# bicyclelab-manager-v3.net
KiCad netlist of a schematic drawn in EAGLE
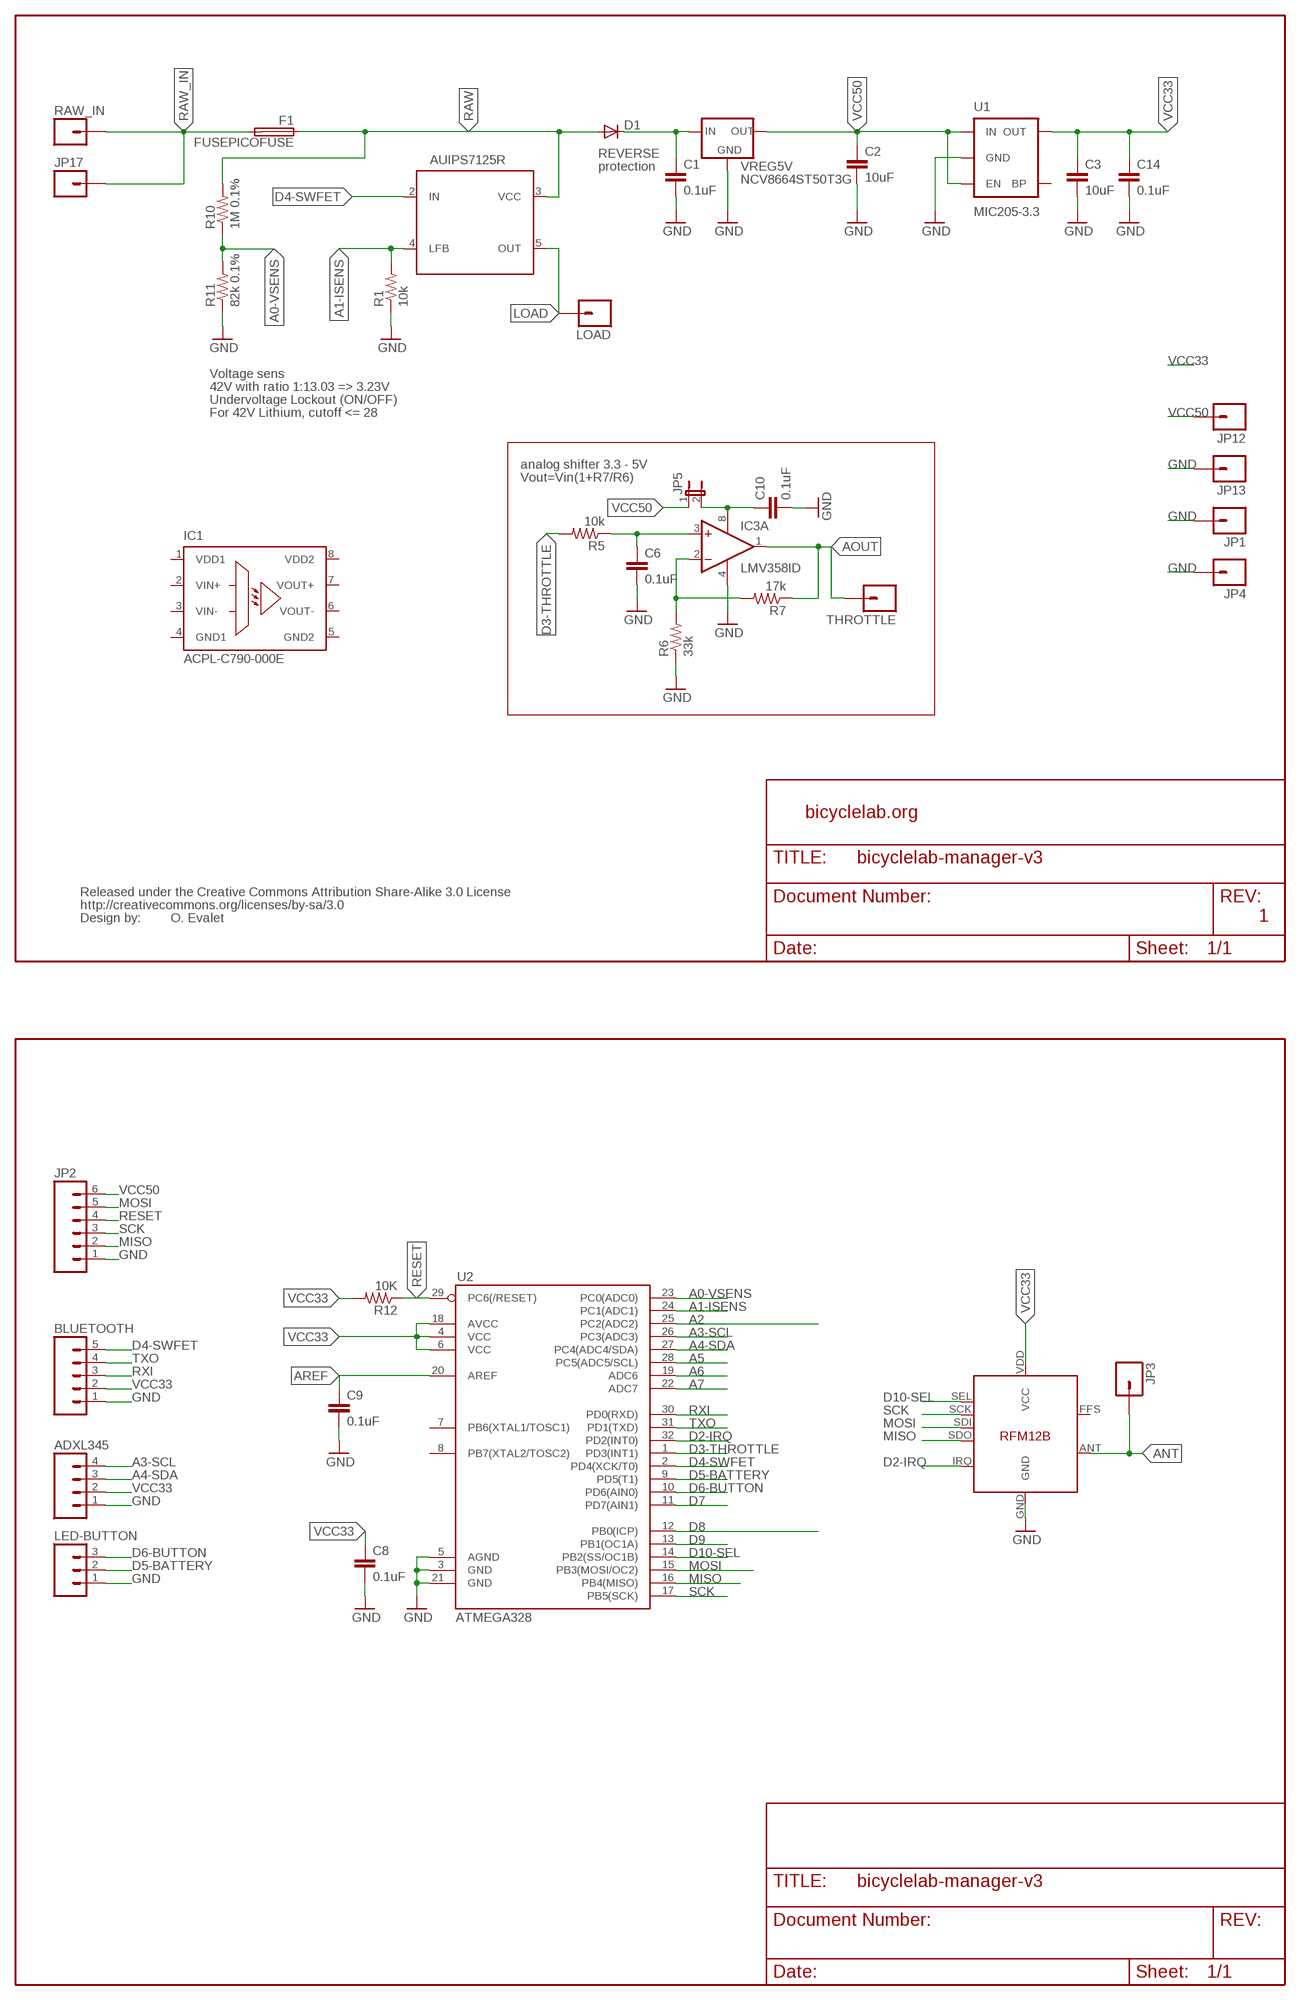
[diagram p0: schematic, sheet 1]

(export (version "E")
  (design (tool "Eeschema 10.0.6"))
  (components
    (comp (ref "ADXL345")
      (value "M04PTH")
      (footprint "eagle-import:1X04")
      (libsource (lib "eagle-import") (part "M04PTH"))
    )
    (comp (ref "BLUETOOTH")
      (value "M05PTH")
      (footprint "eagle-import:1X05")
      (libsource (lib "eagle-import") (part "M05PTH"))
    )
    (comp (ref "C1")
      (value "0.1uF")
      (footprint "eagle-import:0805")
      (libsource (lib "eagle-import") (part "CAP0805"))
    )
    (comp (ref "C2")
      (value "10uF")
      (footprint "eagle-import:0805")
      (libsource (lib "eagle-import") (part "CAP0805"))
    )
    (comp (ref "C3")
      (value "10uF")
      (footprint "eagle-import:0805")
      (libsource (lib "eagle-import") (part "CAP0805"))
    )
    (comp (ref "C6")
      (value "0.1uF")
      (footprint "eagle-import:0805")
      (libsource (lib "eagle-import") (part "CAP0805"))
    )
    (comp (ref "C8")
      (value "0.1uF")
      (footprint "eagle-import:0603-CAP")
      (libsource (lib "eagle-import") (part "CAP0603-CAP"))
    )
    (comp (ref "C9")
      (value "0.1uF")
      (footprint "eagle-import:0603-CAP")
      (libsource (lib "eagle-import") (part "CAP0603-CAP"))
    )
    (comp (ref "C10")
      (value "0.1uF")
      (footprint "eagle-import:0805")
      (libsource (lib "eagle-import") (part "CAP0805"))
    )
    (comp (ref "C14")
      (value "0.1uF")
      (footprint "eagle-import:0603-CAP")
      (libsource (lib "eagle-import") (part "CAP0603-CAP"))
    )
    (comp (ref "D1")
      (value "DIODESOD")
      (footprint "eagle-import:SOD-323")
      (libsource (lib "eagle-import") (part "DIODESOD"))
    )
    (comp (ref "F1")
      (value "FUSEPICOFUSE")
      (footprint "eagle-import:PICOFUSE")
      (libsource (lib "eagle-import") (part "FUSEPICOFUSE"))
    )
    (comp (ref "IC1")
      (value "ACPL-C790-000E")
      (footprint "eagle-import:DIP8")
      (libsource (lib "eagle-import") (part "ACPL-790A"))
    )
    (comp (ref "IC3")
      (value "LMV358ID")
      (footprint "eagle-import:SO08")
      (libsource (lib "eagle-import") (part "MCP602SN"))
    )
    (comp (ref "JP1")
      (value "M01PTH_2MM")
      (footprint "eagle-import:1X01_2MM")
      (libsource (lib "eagle-import") (part "SparkFun_M01PTH_2MM"))
    )
    (comp (ref "JP2")
      (value "M06EM406")
      (footprint "eagle-import:EM406")
      (libsource (lib "eagle-import") (part "M06EM406"))
    )
    (comp (ref "JP3")
      (value "M01SMD-4.5X1.5")
      (footprint "eagle-import:PAD-1.5X4.5")
      (libsource (lib "eagle-import") (part "M01SMD-4.5X1.5"))
    )
    (comp (ref "JP4")
      (value "M01PTH_2MM")
      (footprint "eagle-import:1X01_2MM")
      (libsource (lib "eagle-import") (part "SparkFun_M01PTH_2MM"))
    )
    (comp (ref "JP5")
      (value "JUMPER-2PTH_LOCK")
      (footprint "eagle-import:1X02_LOCK")
      (libsource (lib "eagle-import") (part "JUMPER-2PTH_LOCK"))
    )
    (comp (ref "JP12")
      (value "M01PTH")
      (footprint "eagle-import:1X01")
      (libsource (lib "eagle-import") (part "SparkFun_M01PTH"))
    )
    (comp (ref "JP13")
      (value "M01PTH")
      (footprint "eagle-import:1X01")
      (libsource (lib "eagle-import") (part "SparkFun_M01PTH"))
    )
    (comp (ref "JP17")
      (value "M01PTH_2MM")
      (footprint "eagle-import:1X01_2MM")
      (libsource (lib "eagle-import") (part "SparkFun_M01PTH_2MM"))
    )
    (comp (ref "LED-BUTTON")
      (value "M03PTH")
      (footprint "eagle-import:1X03")
      (libsource (lib "eagle-import") (part "M03PTH"))
    )
    (comp (ref "LOAD")
      (value "M01PTH_2MM")
      (footprint "eagle-import:1X01_2MM")
      (libsource (lib "eagle-import") (part "SparkFun_M01PTH_2MM"))
    )
    (comp (ref "R1")
      (value "10k")
      (footprint "eagle-import:0805")
      (libsource (lib "eagle-import") (part "RESISTOR"))
    )
    (comp (ref "R5")
      (value "10k")
      (footprint "eagle-import:0805")
      (libsource (lib "eagle-import") (part "RESISTOR"))
    )
    (comp (ref "R6")
      (value "33k")
      (footprint "eagle-import:0805")
      (libsource (lib "eagle-import") (part "RESISTOR"))
    )
    (comp (ref "R7")
      (value "17k")
      (footprint "eagle-import:0805")
      (libsource (lib "eagle-import") (part "RESISTOR"))
    )
    (comp (ref "R10")
      (value "1M 0.1%")
      (footprint "eagle-import:0805")
      (libsource (lib "eagle-import") (part "RESISTOR"))
    )
    (comp (ref "R11")
      (value "82k 0.1%")
      (footprint "eagle-import:0805")
      (libsource (lib "eagle-import") (part "RESISTOR"))
    )
    (comp (ref "R12")
      (value "10K")
      (footprint "eagle-import:0603-RES")
      (libsource (lib "eagle-import") (part "RESISTOR0603-RES"))
    )
    (comp (ref "RAW_IN")
      (value "M01PTH_2MM")
      (footprint "eagle-import:1X01_2MM")
      (libsource (lib "eagle-import") (part "SparkFun_M01PTH_2MM"))
    )
    (comp (ref "THROTTLE")
      (value "M01PTH")
      (footprint "eagle-import:1X01")
      (libsource (lib "eagle-import") (part "SparkFun_M01PTH"))
    )
    (comp (ref "U$1")
      (value "RFM12B")
      (footprint "eagle-import:RFM12B")
      (libsource (lib "eagle-import") (part "RFM12B"))
    )
    (comp (ref "U$5")
      (value "CREATIVE_COMMONS")
      (footprint "eagle-import:CREATIVE_COMMONS")
      (libsource (lib "eagle-import") (part "CREATIVE_COMMONS"))
    )
    (comp (ref "U$8")
      (value "AUIPS7125R")
      (footprint "eagle-import:DPAK-5")
      (libsource (lib "eagle-import") (part "AUIPS7125R"))
    )
    (comp (ref "U1")
      (value "MIC205-3.3")
      (footprint "eagle-import:SOT23-5")
      (libsource (lib "eagle-import") (part "V_REG_LDOSMD"))
    )
    (comp (ref "U2")
      (value "ATMEGA328")
      (footprint "eagle-import:TQFP32-08")
      (libsource (lib "eagle-import") (part "ATMEGA168"))
    )
    (comp (ref "VREG5V")
      (value "NCV8664ST50T3G")
      (footprint "eagle-import:SOT223")
      (libsource (lib "eagle-import") (part "V_REG_MIC2920"))
    )
  )
  (nets
    (net (code "1") (name "/A2") (class "Default")
      (node (ref "U2") (pin "25") (pinfunction "PC2(ADC2)_25") (pintype "bidirectional"))
    )
    (net (code "2") (name "/A3-SCL") (class "Default")
      (node (ref "ADXL345") (pin "4") (pinfunction "4_4") (pintype "passive"))
      (node (ref "U2") (pin "26") (pinfunction "PC3(ADC3)_26") (pintype "bidirectional"))
    )
    (net (code "3") (name "/A4-SDA") (class "Default")
      (node (ref "ADXL345") (pin "3") (pinfunction "3_3") (pintype "passive"))
      (node (ref "U2") (pin "27") (pinfunction "PC4(ADC4/SDA)_27") (pintype "bidirectional"))
    )
    (net (code "4") (name "/A5") (class "Default")
      (node (ref "U2") (pin "28") (pinfunction "PC5(ADC5/SCL)_28") (pintype "bidirectional"))
    )
    (net (code "5") (name "/A6") (class "Default")
      (node (ref "U2") (pin "19") (pinfunction "ADC6_19") (pintype "bidirectional"))
    )
    (net (code "6") (name "/A7") (class "Default")
      (node (ref "U2") (pin "22") (pinfunction "ADC7_22") (pintype "bidirectional"))
    )
    (net (code "7") (name "/D2-IRQ") (class "Default")
      (node (ref "U$1") (pin "IRQ") (pinfunction "IRQ_IRQ") (pintype "open_collector"))
      (node (ref "U2") (pin "32") (pinfunction "PD2(INT0)_32") (pintype "bidirectional"))
    )
    (net (code "8") (name "/D5-BATTERY") (class "Default")
      (node (ref "LED-BUTTON") (pin "2") (pinfunction "2_2") (pintype "passive"))
      (node (ref "U2") (pin "9") (pinfunction "PD5(T1)_9") (pintype "bidirectional"))
    )
    (net (code "9") (name "/D6-BUTTON") (class "Default")
      (node (ref "LED-BUTTON") (pin "3") (pinfunction "3_3") (pintype "passive"))
      (node (ref "U2") (pin "10") (pinfunction "PD6(AIN0)_10") (pintype "bidirectional"))
    )
    (net (code "10") (name "/D7") (class "Default")
      (node (ref "U2") (pin "11") (pinfunction "PD7(AIN1)_11") (pintype "bidirectional"))
    )
    (net (code "11") (name "/D8") (class "Default")
      (node (ref "U2") (pin "12") (pinfunction "PB0(ICP)_12") (pintype "bidirectional"))
    )
    (net (code "12") (name "/D9") (class "Default")
      (node (ref "U2") (pin "13") (pinfunction "PB1(OC1A)_13") (pintype "bidirectional"))
    )
    (net (code "13") (name "/D10-SEL") (class "Default")
      (node (ref "U$1") (pin "SEL") (pinfunction "SEL_SEL") (pintype "input"))
      (node (ref "U2") (pin "14") (pinfunction "PB2(SS/OC1B)_14") (pintype "bidirectional"))
    )
    (net (code "14") (name "/GND1") (class "Default")
      (node (ref "IC1") (pin "4") (pinfunction "GND1_4") (pintype "power_in"))
    )
    (net (code "15") (name "/GND2") (class "Default")
      (node (ref "IC1") (pin "5") (pinfunction "GND2_5") (pintype "power_in"))
    )
    (net (code "16") (name "/MISO") (class "Default")
      (node (ref "JP2") (pin "2") (pinfunction "2_2") (pintype "passive"))
      (node (ref "U$1") (pin "SDO") (pinfunction "SDO_SDO") (pintype "output"))
      (node (ref "U2") (pin "16") (pinfunction "PB4(MISO)_16") (pintype "bidirectional"))
    )
    (net (code "17") (name "/MOSI") (class "Default")
      (node (ref "JP2") (pin "5") (pinfunction "5_5") (pintype "passive"))
      (node (ref "U$1") (pin "SDI") (pinfunction "SDI_SDI") (pintype "input"))
      (node (ref "U2") (pin "15") (pinfunction "PB3(MOSI/OC2)_15") (pintype "bidirectional"))
    )
    (net (code "18") (name "/RXI") (class "Default")
      (node (ref "BLUETOOTH") (pin "3") (pinfunction "3_3") (pintype "passive"))
      (node (ref "U2") (pin "30") (pinfunction "PD0(RXD)_30") (pintype "bidirectional"))
    )
    (net (code "19") (name "/SCK") (class "Default")
      (node (ref "JP2") (pin "3") (pinfunction "3_3") (pintype "passive"))
      (node (ref "U$1") (pin "SCK") (pinfunction "SCK_SCK") (pintype "input"))
      (node (ref "U2") (pin "17") (pinfunction "PB5(SCK)_17") (pintype "bidirectional"))
    )
    (net (code "20") (name "/TXO") (class "Default")
      (node (ref "BLUETOOTH") (pin "4") (pinfunction "4_4") (pintype "passive"))
      (node (ref "U2") (pin "31") (pinfunction "PD1(TXD)_31") (pintype "bidirectional"))
    )
    (net (code "21") (name "/VDD1") (class "Default")
      (node (ref "IC1") (pin "1") (pinfunction "VDD1_1") (pintype "power_in"))
    )
    (net (code "22") (name "/VDD2") (class "Default")
      (node (ref "IC1") (pin "8") (pinfunction "VDD2_8") (pintype "power_in"))
    )
    (net (code "23") (name "/VIN+") (class "Default")
      (node (ref "IC1") (pin "2") (pinfunction "VIN+_2") (pintype "power_in"))
    )
    (net (code "24") (name "/VIN-") (class "Default")
      (node (ref "IC1") (pin "3") (pinfunction "VIN-_3") (pintype "power_in"))
    )
    (net (code "25") (name "/VOUT+") (class "Default")
      (node (ref "IC1") (pin "7") (pinfunction "VOUT+_7") (pintype "power_in"))
    )
    (net (code "26") (name "/VOUT-") (class "Default")
      (node (ref "IC1") (pin "6") (pinfunction "VOUT-_6") (pintype "power_in"))
    )
    (net (code "27") (name "A0-VSENS") (class "Default")
      (node (ref "R10") (pin "1") (pinfunction "1_1") (pintype "passive"))
      (node (ref "R11") (pin "2") (pinfunction "2_2") (pintype "passive"))
      (node (ref "U2") (pin "23") (pinfunction "PC0(ADC0)_23") (pintype "bidirectional"))
    )
    (net (code "28") (name "A1-ISENS") (class "Default")
      (node (ref "R1") (pin "2") (pinfunction "2_2") (pintype "passive"))
      (node (ref "U$8") (pin "4") (pinfunction "LFB_4") (pintype "output"))
      (node (ref "U2") (pin "24") (pinfunction "PC1(ADC1)_24") (pintype "bidirectional"))
    )
    (net (code "29") (name "ANT") (class "Default")
      (node (ref "JP3") (pin "P$1") (pinfunction "1_P$1") (pintype "passive"))
      (node (ref "U$1") (pin "ANT") (pinfunction "ANT_ANT") (pintype "passive"))
    )
    (net (code "30") (name "AOUT") (class "Default")
      (node (ref "IC3") (pin "1") (pinfunction "OUT_1") (pintype "output"))
      (node (ref "R7") (pin "1") (pinfunction "1_1") (pintype "passive"))
      (node (ref "THROTTLE") (pin "1") (pinfunction "1_1") (pintype "passive"))
    )
    (net (code "31") (name "AREF") (class "Default")
      (node (ref "C9") (pin "1") (pinfunction "1_1") (pintype "passive"))
      (node (ref "U2") (pin "20") (pinfunction "AREF_20") (pintype "bidirectional"))
    )
    (net (code "32") (name "D3-THROTTLE") (class "Default")
      (node (ref "R5") (pin "2") (pinfunction "2_2") (pintype "passive"))
      (node (ref "U2") (pin "1") (pinfunction "PD3(INT1)_1") (pintype "bidirectional"))
    )
    (net (code "33") (name "D4-SWFET") (class "Default")
      (node (ref "BLUETOOTH") (pin "5") (pinfunction "5_5") (pintype "passive"))
      (node (ref "U$8") (pin "2") (pinfunction "IN_2") (pintype "input"))
      (node (ref "U2") (pin "2") (pinfunction "PD4(XCK/T0)_2") (pintype "bidirectional"))
    )
    (net (code "34") (name "GND") (class "Default")
      (node (ref "ADXL345") (pin "1") (pinfunction "1_1") (pintype "passive"))
      (node (ref "BLUETOOTH") (pin "1") (pinfunction "1_1") (pintype "passive"))
      (node (ref "C1") (pin "2") (pinfunction "2_2") (pintype "passive"))
      (node (ref "C10") (pin "2") (pinfunction "2_2") (pintype "passive"))
      (node (ref "C14") (pin "2") (pinfunction "2_2") (pintype "passive"))
      (node (ref "C2") (pin "2") (pinfunction "2_2") (pintype "passive"))
      (node (ref "C3") (pin "2") (pinfunction "2_2") (pintype "passive"))
      (node (ref "C6") (pin "2") (pinfunction "2_2") (pintype "passive"))
      (node (ref "C8") (pin "2") (pinfunction "2_2") (pintype "passive"))
      (node (ref "C9") (pin "2") (pinfunction "2_2") (pintype "passive"))
      (node (ref "IC3") (pin "4") (pinfunction "V-_4") (pintype "power_in"))
      (node (ref "JP1") (pin "1") (pinfunction "1_1") (pintype "passive"))
      (node (ref "JP13") (pin "1") (pinfunction "1_1") (pintype "passive"))
      (node (ref "JP2") (pin "1") (pinfunction "1_1") (pintype "passive"))
      (node (ref "JP4") (pin "1") (pinfunction "1_1") (pintype "passive"))
      (node (ref "LED-BUTTON") (pin "1") (pinfunction "1_1") (pintype "passive"))
      (node (ref "R1") (pin "1") (pinfunction "1_1") (pintype "passive"))
      (node (ref "R11") (pin "1") (pinfunction "1_1") (pintype "passive"))
      (node (ref "R6") (pin "1") (pinfunction "1_1") (pintype "passive"))
      (node (ref "U$1") (pin "GND") (pinfunction "GND_GND") (pintype "power_in"))
      (node (ref "U1") (pin "2") (pinfunction "GND_2") (pintype "input"))
      (node (ref "U2") (pin "21") (pinfunction "GND_21") (pintype "bidirectional"))
      (node (ref "U2") (pin "3") (pinfunction "GND_3") (pintype "bidirectional"))
      (node (ref "U2") (pin "5") (pinfunction "AGND_5") (pintype "bidirectional"))
      (node (ref "VREG5V") (pin "2") (pinfunction "GND_2") (pintype "input"))
    )
    (net (code "35") (name "LOAD") (class "Default")
      (node (ref "LOAD") (pin "1") (pinfunction "1_1") (pintype "passive"))
      (node (ref "U$8") (pin "5") (pinfunction "OUT_5") (pintype "output"))
    )
    (net (code "36") (name "Net-(D1-C)") (class "Default")
      (node (ref "C1") (pin "1") (pinfunction "1_1") (pintype "passive"))
      (node (ref "D1") (pin "1") (pinfunction "C_1") (pintype "passive"))
      (node (ref "VREG5V") (pin "1") (pinfunction "IN_1") (pintype "input"))
    )
    (net (code "37") (name "Net-(IC3A-+IN)") (class "Default")
      (node (ref "C6") (pin "1") (pinfunction "1_1") (pintype "passive"))
      (node (ref "IC3") (pin "3") (pinfunction "+IN_3") (pintype "input"))
      (node (ref "R5") (pin "1") (pinfunction "1_1") (pintype "passive"))
    )
    (net (code "38") (name "Net-(IC3A--IN)") (class "Default")
      (node (ref "IC3") (pin "2") (pinfunction "-IN_2") (pintype "input"))
      (node (ref "R6") (pin "2") (pinfunction "2_2") (pintype "passive"))
      (node (ref "R7") (pin "2") (pinfunction "2_2") (pintype "passive"))
    )
    (net (code "39") (name "Net-(IC3C-V+)") (class "Default")
      (node (ref "C10") (pin "1") (pinfunction "1_1") (pintype "passive"))
      (node (ref "IC3") (pin "8") (pinfunction "V+_8") (pintype "power_in"))
      (node (ref "JP5") (pin "2") (pinfunction "2_2") (pintype "passive"))
    )
    (net (code "40") (name "RAW") (class "Default")
      (node (ref "D1") (pin "2") (pinfunction "A_2") (pintype "passive"))
      (node (ref "F1") (pin "1") (pinfunction "1_1") (pintype "passive"))
      (node (ref "R10") (pin "2") (pinfunction "2_2") (pintype "passive"))
      (node (ref "U$8") (pin "3") (pinfunction "VCC_3") (pintype "input"))
    )
    (net (code "41") (name "RAW_IN") (class "Default")
      (node (ref "F1") (pin "2") (pinfunction "2_2") (pintype "passive"))
      (node (ref "JP17") (pin "1") (pinfunction "1_1") (pintype "passive"))
      (node (ref "RAW_IN") (pin "1") (pinfunction "1_1") (pintype "passive"))
    )
    (net (code "42") (name "RESET") (class "Default")
      (node (ref "JP2") (pin "4") (pinfunction "4_4") (pintype "passive"))
      (node (ref "R12") (pin "1") (pinfunction "1_1") (pintype "passive"))
      (node (ref "U2") (pin "29") (pinfunction "PC6(/RESET)_29") (pintype "bidirectional"))
    )
    (net (code "43") (name "VCC33") (class "Default")
      (node (ref "ADXL345") (pin "2") (pinfunction "2_2") (pintype "passive"))
      (node (ref "BLUETOOTH") (pin "2") (pinfunction "2_2") (pintype "passive"))
      (node (ref "C14") (pin "1") (pinfunction "1_1") (pintype "passive"))
      (node (ref "C3") (pin "1") (pinfunction "1_1") (pintype "passive"))
      (node (ref "C8") (pin "1") (pinfunction "1_1") (pintype "passive"))
      (node (ref "R12") (pin "2") (pinfunction "2_2") (pintype "passive"))
      (node (ref "U$1") (pin "VDD") (pinfunction "VCC_VDD") (pintype "power_in"))
      (node (ref "U1") (pin "5") (pinfunction "OUT_5") (pintype "passive"))
      (node (ref "U2") (pin "18") (pinfunction "AVCC_18") (pintype "bidirectional"))
      (node (ref "U2") (pin "4") (pinfunction "VCC_4") (pintype "bidirectional"))
      (node (ref "U2") (pin "6") (pinfunction "VCC_6") (pintype "bidirectional"))
    )
    (net (code "44") (name "VCC50") (class "Default")
      (node (ref "C2") (pin "1") (pinfunction "1_1") (pintype "passive"))
      (node (ref "JP12") (pin "1") (pinfunction "1_1") (pintype "passive"))
      (node (ref "JP2") (pin "6") (pinfunction "6_6") (pintype "passive"))
      (node (ref "JP5") (pin "1") (pinfunction "1_1") (pintype "passive"))
      (node (ref "U1") (pin "1") (pinfunction "IN_1") (pintype "input"))
      (node (ref "U1") (pin "3") (pinfunction "EN_3") (pintype "input"))
      (node (ref "VREG5V") (pin "3") (pinfunction "OUT_3") (pintype "output"))
    )
    (net (code "45") (name "unconnected-(U$1-PadFFS)") (class "Default")
      (node (ref "U$1") (pin "FFS") (pinfunction "FFS_FFS") (pintype "bidirectional"))
    )
    (net (code "46") (name "unconnected-(U$8-NC-Pad1)") (class "Default")
      (node (ref "U$8") (pin "1") (pinfunction "NC_1") (pintype "no_connect"))
    )
    (net (code "47") (name "unconnected-(U1-BP-Pad4)") (class "Default")
      (node (ref "U1") (pin "4") (pinfunction "BP_4") (pintype "input"))
    )
    (net (code "48") (name "unconnected-(U2-PB6(XTAL1{slash}TOSC1)-Pad7)") (class "Default")
      (node (ref "U2") (pin "7") (pinfunction "PB6(XTAL1/TOSC1)_7") (pintype "bidirectional"))
    )
    (net (code "49") (name "unconnected-(U2-PB7(XTAL2{slash}TOSC2)-Pad8)") (class "Default")
      (node (ref "U2") (pin "8") (pinfunction "PB7(XTAL2/TOSC2)_8") (pintype "bidirectional"))
    )
  )
)
